# power.net
KiCad netlist of a schematic drawn in EAGLE
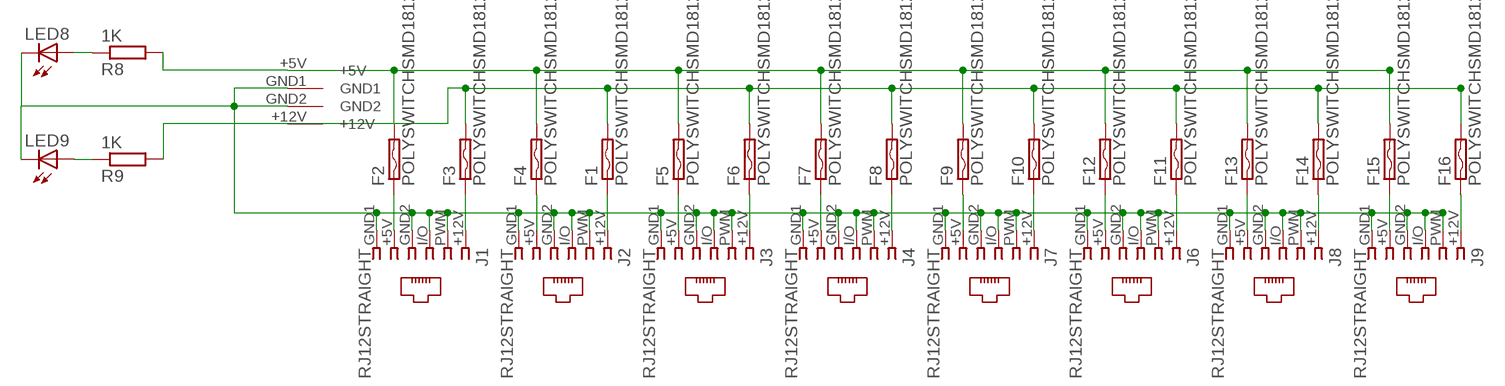
[diagram p0: schematic, sheet 1]

(export (version "E")
  (design (tool "Eeschema 10.0.6"))
  (components
    (comp (ref "F1")
      (value "POLYSWITCHSMD1812")
      (footprint "eagle-import:C1812")
      (libsource (lib "eagle-import") (part "POLYSWITCHSMD1812"))
    )
    (comp (ref "F2")
      (value "POLYSWITCHSMD1812")
      (footprint "eagle-import:C1812")
      (libsource (lib "eagle-import") (part "POLYSWITCHSMD1812"))
    )
    (comp (ref "F3")
      (value "POLYSWITCHSMD1812")
      (footprint "eagle-import:C1812")
      (libsource (lib "eagle-import") (part "POLYSWITCHSMD1812"))
    )
    (comp (ref "F4")
      (value "POLYSWITCHSMD1812")
      (footprint "eagle-import:C1812")
      (libsource (lib "eagle-import") (part "POLYSWITCHSMD1812"))
    )
    (comp (ref "F5")
      (value "POLYSWITCHSMD1812")
      (footprint "eagle-import:C1812")
      (libsource (lib "eagle-import") (part "POLYSWITCHSMD1812"))
    )
    (comp (ref "F6")
      (value "POLYSWITCHSMD1812")
      (footprint "eagle-import:C1812")
      (libsource (lib "eagle-import") (part "POLYSWITCHSMD1812"))
    )
    (comp (ref "F7")
      (value "POLYSWITCHSMD1812")
      (footprint "eagle-import:C1812")
      (libsource (lib "eagle-import") (part "POLYSWITCHSMD1812"))
    )
    (comp (ref "F8")
      (value "POLYSWITCHSMD1812")
      (footprint "eagle-import:C1812")
      (libsource (lib "eagle-import") (part "POLYSWITCHSMD1812"))
    )
    (comp (ref "F9")
      (value "POLYSWITCHSMD1812")
      (footprint "eagle-import:C1812")
      (libsource (lib "eagle-import") (part "POLYSWITCHSMD1812"))
    )
    (comp (ref "F10")
      (value "POLYSWITCHSMD1812")
      (footprint "eagle-import:C1812")
      (libsource (lib "eagle-import") (part "POLYSWITCHSMD1812"))
    )
    (comp (ref "F11")
      (value "POLYSWITCHSMD1812")
      (footprint "eagle-import:C1812")
      (libsource (lib "eagle-import") (part "POLYSWITCHSMD1812"))
    )
    (comp (ref "F12")
      (value "POLYSWITCHSMD1812")
      (footprint "eagle-import:C1812")
      (libsource (lib "eagle-import") (part "POLYSWITCHSMD1812"))
    )
    (comp (ref "F13")
      (value "POLYSWITCHSMD1812")
      (footprint "eagle-import:C1812")
      (libsource (lib "eagle-import") (part "POLYSWITCHSMD1812"))
    )
    (comp (ref "F14")
      (value "POLYSWITCHSMD1812")
      (footprint "eagle-import:C1812")
      (libsource (lib "eagle-import") (part "POLYSWITCHSMD1812"))
    )
    (comp (ref "F15")
      (value "POLYSWITCHSMD1812")
      (footprint "eagle-import:C1812")
      (libsource (lib "eagle-import") (part "POLYSWITCHSMD1812"))
    )
    (comp (ref "F16")
      (value "POLYSWITCHSMD1812")
      (footprint "eagle-import:C1812")
      (libsource (lib "eagle-import") (part "POLYSWITCHSMD1812"))
    )
    (comp (ref "J1")
      (value "RJ12STRAIGHT")
      (footprint "eagle-import:RJ12-STRAIGHT")
      (libsource (lib "eagle-import") (part "RJ12STRAIGHT"))
    )
    (comp (ref "J2")
      (value "RJ12STRAIGHT")
      (footprint "eagle-import:RJ12-STRAIGHT")
      (libsource (lib "eagle-import") (part "RJ12STRAIGHT"))
    )
    (comp (ref "J3")
      (value "RJ12STRAIGHT")
      (footprint "eagle-import:RJ12-STRAIGHT")
      (libsource (lib "eagle-import") (part "RJ12STRAIGHT"))
    )
    (comp (ref "J4")
      (value "RJ12STRAIGHT")
      (footprint "eagle-import:RJ12-STRAIGHT")
      (libsource (lib "eagle-import") (part "RJ12STRAIGHT"))
    )
    (comp (ref "J6")
      (value "RJ12STRAIGHT")
      (footprint "eagle-import:RJ12-STRAIGHT")
      (libsource (lib "eagle-import") (part "RJ12STRAIGHT"))
    )
    (comp (ref "J7")
      (value "RJ12STRAIGHT")
      (footprint "eagle-import:RJ12-STRAIGHT")
      (libsource (lib "eagle-import") (part "RJ12STRAIGHT"))
    )
    (comp (ref "J8")
      (value "RJ12STRAIGHT")
      (footprint "eagle-import:RJ12-STRAIGHT")
      (libsource (lib "eagle-import") (part "RJ12STRAIGHT"))
    )
    (comp (ref "J9")
      (value "RJ12STRAIGHT")
      (footprint "eagle-import:RJ12-STRAIGHT")
      (libsource (lib "eagle-import") (part "RJ12STRAIGHT"))
    )
    (comp (ref "LED8")
      (value "LED3MM")
      (footprint "eagle-import:LED3MM")
      (libsource (lib "eagle-import") (part "LED3MM"))
    )
    (comp (ref "LED9")
      (value "LED3MM")
      (footprint "eagle-import:LED3MM")
      (libsource (lib "eagle-import") (part "LED3MM"))
    )
    (comp (ref "R8")
      (value "1K")
      (footprint "eagle-import:M1206")
      (libsource (lib "eagle-import") (part "R-EU_M1206"))
    )
    (comp (ref "R9")
      (value "1K")
      (footprint "eagle-import:M1206")
      (libsource (lib "eagle-import") (part "R-EU_M1206"))
    )
    (comp (ref "U$1")
      (value "KPJX-4S-S")
      (footprint "eagle-import:KPJX-4S-S")
      (libsource (lib "eagle-import") (part "KPJX-4S-S"))
    )
  )
  (nets
    (net (code "1") (name "Net-(F1-Pad2)") (class "Default")
      (node (ref "F1") (pin "2") (pinfunction "2_2") (pintype "passive"))
      (node (ref "F10") (pin "2") (pinfunction "2_2") (pintype "passive"))
      (node (ref "F11") (pin "2") (pinfunction "2_2") (pintype "passive"))
      (node (ref "F14") (pin "2") (pinfunction "2_2") (pintype "passive"))
      (node (ref "F16") (pin "2") (pinfunction "2_2") (pintype "passive"))
      (node (ref "F3") (pin "2") (pinfunction "2_2") (pintype "passive"))
      (node (ref "F6") (pin "2") (pinfunction "2_2") (pintype "passive"))
      (node (ref "F8") (pin "2") (pinfunction "2_2") (pintype "passive"))
      (node (ref "R9") (pin "2") (pinfunction "2_2") (pintype "passive"))
      (node (ref "U$1") (pin "+12V") (pinfunction "+12V_+12V") (pintype "power_in"))
    )
    (net (code "2") (name "Net-(F12-Pad2)") (class "Default")
      (node (ref "F12") (pin "2") (pinfunction "2_2") (pintype "passive"))
      (node (ref "F13") (pin "2") (pinfunction "2_2") (pintype "passive"))
      (node (ref "F15") (pin "2") (pinfunction "2_2") (pintype "passive"))
      (node (ref "F2") (pin "2") (pinfunction "2_2") (pintype "passive"))
      (node (ref "F4") (pin "2") (pinfunction "2_2") (pintype "passive"))
      (node (ref "F5") (pin "2") (pinfunction "2_2") (pintype "passive"))
      (node (ref "F7") (pin "2") (pinfunction "2_2") (pintype "passive"))
      (node (ref "F9") (pin "2") (pinfunction "2_2") (pintype "passive"))
      (node (ref "R8") (pin "2") (pinfunction "2_2") (pintype "passive"))
      (node (ref "U$1") (pin "+5V") (pinfunction "+5V_+5V") (pintype "power_in"))
    )
    (net (code "3") (name "Net-(J1-1)") (class "Default")
      (node (ref "F3") (pin "1") (pinfunction "1_1") (pintype "passive"))
      (node (ref "J1") (pin "+12V") (pinfunction "1_+12V") (pintype "power_in"))
    )
    (net (code "4") (name "Net-(J1-2)") (class "Default")
      (node (ref "J1") (pin "GND1") (pinfunction "6_GND1") (pintype "power_in"))
      (node (ref "J1") (pin "GND2") (pinfunction "4_GND2") (pintype "power_in"))
      (node (ref "J1") (pin "I/O") (pinfunction "3_I/O") (pintype "bidirectional"))
      (node (ref "J1") (pin "PWM") (pinfunction "2_PWM") (pintype "bidirectional"))
      (node (ref "J2") (pin "GND1") (pinfunction "6_GND1") (pintype "power_in"))
      (node (ref "J2") (pin "GND2") (pinfunction "4_GND2") (pintype "power_in"))
      (node (ref "J2") (pin "I/O") (pinfunction "3_I/O") (pintype "bidirectional"))
      (node (ref "J2") (pin "PWM") (pinfunction "2_PWM") (pintype "bidirectional"))
      (node (ref "J3") (pin "GND1") (pinfunction "6_GND1") (pintype "power_in"))
      (node (ref "J3") (pin "GND2") (pinfunction "4_GND2") (pintype "power_in"))
      (node (ref "J3") (pin "I/O") (pinfunction "3_I/O") (pintype "bidirectional"))
      (node (ref "J3") (pin "PWM") (pinfunction "2_PWM") (pintype "bidirectional"))
      (node (ref "J4") (pin "GND1") (pinfunction "6_GND1") (pintype "power_in"))
      (node (ref "J4") (pin "GND2") (pinfunction "4_GND2") (pintype "power_in"))
      (node (ref "J4") (pin "I/O") (pinfunction "3_I/O") (pintype "bidirectional"))
      (node (ref "J4") (pin "PWM") (pinfunction "2_PWM") (pintype "bidirectional"))
      (node (ref "J6") (pin "GND1") (pinfunction "6_GND1") (pintype "power_in"))
      (node (ref "J6") (pin "GND2") (pinfunction "4_GND2") (pintype "power_in"))
      (node (ref "J6") (pin "I/O") (pinfunction "3_I/O") (pintype "bidirectional"))
      (node (ref "J6") (pin "PWM") (pinfunction "2_PWM") (pintype "bidirectional"))
      (node (ref "J7") (pin "GND1") (pinfunction "6_GND1") (pintype "power_in"))
      (node (ref "J7") (pin "GND2") (pinfunction "4_GND2") (pintype "power_in"))
      (node (ref "J7") (pin "I/O") (pinfunction "3_I/O") (pintype "bidirectional"))
      (node (ref "J7") (pin "PWM") (pinfunction "2_PWM") (pintype "bidirectional"))
      (node (ref "J8") (pin "GND1") (pinfunction "6_GND1") (pintype "power_in"))
      (node (ref "J8") (pin "GND2") (pinfunction "4_GND2") (pintype "power_in"))
      (node (ref "J8") (pin "I/O") (pinfunction "3_I/O") (pintype "bidirectional"))
      (node (ref "J8") (pin "PWM") (pinfunction "2_PWM") (pintype "bidirectional"))
      (node (ref "J9") (pin "GND1") (pinfunction "6_GND1") (pintype "power_in"))
      (node (ref "J9") (pin "GND2") (pinfunction "4_GND2") (pintype "power_in"))
      (node (ref "J9") (pin "I/O") (pinfunction "3_I/O") (pintype "bidirectional"))
      (node (ref "J9") (pin "PWM") (pinfunction "2_PWM") (pintype "bidirectional"))
      (node (ref "LED8") (pin "K") (pinfunction "C_K") (pintype "passive"))
      (node (ref "LED9") (pin "K") (pinfunction "C_K") (pintype "passive"))
      (node (ref "U$1") (pin "GND1") (pinfunction "GND1_GND1") (pintype "input"))
      (node (ref "U$1") (pin "GND2") (pinfunction "GND2_GND2") (pintype "input"))
    )
    (net (code "5") (name "Net-(J1-5)") (class "Default")
      (node (ref "F2") (pin "1") (pinfunction "1_1") (pintype "passive"))
      (node (ref "J1") (pin "+5V") (pinfunction "5_+5V") (pintype "power_in"))
    )
    (net (code "6") (name "Net-(J2-1)") (class "Default")
      (node (ref "F1") (pin "1") (pinfunction "1_1") (pintype "passive"))
      (node (ref "J2") (pin "+12V") (pinfunction "1_+12V") (pintype "power_in"))
    )
    (net (code "7") (name "Net-(J2-5)") (class "Default")
      (node (ref "F4") (pin "1") (pinfunction "1_1") (pintype "passive"))
      (node (ref "J2") (pin "+5V") (pinfunction "5_+5V") (pintype "power_in"))
    )
    (net (code "8") (name "Net-(J3-1)") (class "Default")
      (node (ref "F6") (pin "1") (pinfunction "1_1") (pintype "passive"))
      (node (ref "J3") (pin "+12V") (pinfunction "1_+12V") (pintype "power_in"))
    )
    (net (code "9") (name "Net-(J3-5)") (class "Default")
      (node (ref "F5") (pin "1") (pinfunction "1_1") (pintype "passive"))
      (node (ref "J3") (pin "+5V") (pinfunction "5_+5V") (pintype "power_in"))
    )
    (net (code "10") (name "Net-(J4-1)") (class "Default")
      (node (ref "F8") (pin "1") (pinfunction "1_1") (pintype "passive"))
      (node (ref "J4") (pin "+12V") (pinfunction "1_+12V") (pintype "power_in"))
    )
    (net (code "11") (name "Net-(J4-5)") (class "Default")
      (node (ref "F7") (pin "1") (pinfunction "1_1") (pintype "passive"))
      (node (ref "J4") (pin "+5V") (pinfunction "5_+5V") (pintype "power_in"))
    )
    (net (code "12") (name "Net-(J6-1)") (class "Default")
      (node (ref "F11") (pin "1") (pinfunction "1_1") (pintype "passive"))
      (node (ref "J6") (pin "+12V") (pinfunction "1_+12V") (pintype "power_in"))
    )
    (net (code "13") (name "Net-(J6-5)") (class "Default")
      (node (ref "F12") (pin "1") (pinfunction "1_1") (pintype "passive"))
      (node (ref "J6") (pin "+5V") (pinfunction "5_+5V") (pintype "power_in"))
    )
    (net (code "14") (name "Net-(J7-1)") (class "Default")
      (node (ref "F10") (pin "1") (pinfunction "1_1") (pintype "passive"))
      (node (ref "J7") (pin "+12V") (pinfunction "1_+12V") (pintype "power_in"))
    )
    (net (code "15") (name "Net-(J7-5)") (class "Default")
      (node (ref "F9") (pin "1") (pinfunction "1_1") (pintype "passive"))
      (node (ref "J7") (pin "+5V") (pinfunction "5_+5V") (pintype "power_in"))
    )
    (net (code "16") (name "Net-(J8-1)") (class "Default")
      (node (ref "F14") (pin "1") (pinfunction "1_1") (pintype "passive"))
      (node (ref "J8") (pin "+12V") (pinfunction "1_+12V") (pintype "power_in"))
    )
    (net (code "17") (name "Net-(J8-5)") (class "Default")
      (node (ref "F13") (pin "1") (pinfunction "1_1") (pintype "passive"))
      (node (ref "J8") (pin "+5V") (pinfunction "5_+5V") (pintype "power_in"))
    )
    (net (code "18") (name "Net-(J9-1)") (class "Default")
      (node (ref "F16") (pin "1") (pinfunction "1_1") (pintype "passive"))
      (node (ref "J9") (pin "+12V") (pinfunction "1_+12V") (pintype "power_in"))
    )
    (net (code "19") (name "Net-(J9-5)") (class "Default")
      (node (ref "F15") (pin "1") (pinfunction "1_1") (pintype "passive"))
      (node (ref "J9") (pin "+5V") (pinfunction "5_+5V") (pintype "power_in"))
    )
    (net (code "20") (name "Net-(LED8-PadA)") (class "Default")
      (node (ref "LED8") (pin "A") (pinfunction "A_A") (pintype "passive"))
      (node (ref "R8") (pin "1") (pinfunction "1_1") (pintype "passive"))
    )
    (net (code "21") (name "Net-(LED9-PadA)") (class "Default")
      (node (ref "LED9") (pin "A") (pinfunction "A_A") (pintype "passive"))
      (node (ref "R9") (pin "1") (pinfunction "1_1") (pintype "passive"))
    )
  )
)
